# PSU_MAX1831_1V5_ALT.net
KiCad netlist of a schematic drawn in Altium Designer
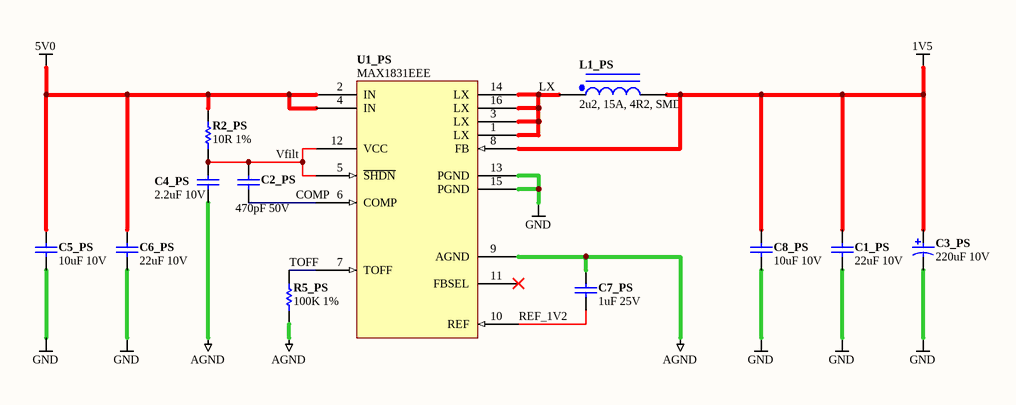
[diagram p0: PSU_MAX1831_1V5_ALT.SchDoc]

(export (version "E")
  (design (tool "Eeschema 10.0.6"))
  (components
    (comp (ref "C1_PS")
      (value "22uF 10V")
      (footprint "CAPC3225-STAR")
      (description "Capacitor, Ceramic, 22uF -20%/+80% 10V 1210 (3225) Y5V")
      (fields (field (name "TOLERANCE") "-20 / +80 %"))
      (libsource (lib "AltiumDesignLibrary") (part "CAP-NP"))
    )
    (comp (ref "C2_PS")
      (value "470pF 50V")
      (footprint "CAPC1005-STAR")
      (description "Capacitor, Ceramic, 470pF 5% 50V 0402 (1005) COG")
      (fields (field (name "TOLERANCE") "5 %"))
      (libsource (lib "AltiumDesignLibrary") (part "CAP-NP"))
    )
    (comp (ref "C3_PS")
      (value "220uF 10V")
      (footprint "CAPC7343-STAR")
      (description "Capacitor, Tantalum, 220uF 10% 10V MCCT-D (7343-31)")
      (fields (field (name "TOLERANCE") "10 %"))
      (libsource (lib "AltiumDesignLibrary") (part "CAP-P"))
    )
    (comp (ref "C4_PS")
      (value "2.2uF 10V")
      (footprint "CAPC1608-STAR")
      (description "Capacitor, Ceramic, 2.2uF 10% 10V 0603 (1608) X5R")
      (fields (field (name "TOLERANCE") "10 %"))
      (libsource (lib "AltiumDesignLibrary") (part "CAP-NP"))
    )
    (comp (ref "C5_PS")
      (value "10uF 10V")
      (footprint "CAPC2012-STAR")
      (description "Capacitor, Ceramic, 10uF 10% 10V 0805 (2012) X5R")
      (fields (field (name "TOLERANCE") "10 %"))
      (libsource (lib "AltiumDesignLibrary") (part "CAP-NP"))
    )
    (comp (ref "C6_PS")
      (value "22uF 10V")
      (footprint "CAPC3225-STAR")
      (description "Capacitor, Ceramic, 22uF -20%/+80% 10V 1210 (3225) Y5V")
      (fields (field (name "TOLERANCE") "-20 / +80 %"))
      (libsource (lib "AltiumDesignLibrary") (part "CAP-NP"))
    )
    (comp (ref "C7_PS")
      (value "1uF 25V")
      (footprint "CAPC3216-STAR")
      (description "Capacitor, Ceramic, 1uF 10% 25V 1206 (3216) X7R")
      (fields (field (name "TOLERANCE") "10 %"))
      (libsource (lib "AltiumDesignLibrary") (part "CAP-NP"))
    )
    (comp (ref "C8_PS")
      (value "10uF 10V")
      (footprint "CAPC2012-STAR")
      (description "Capacitor, Ceramic, 10uF 10% 10V 0805 (2012) X5R")
      (fields (field (name "TOLERANCE") "10 %"))
      (libsource (lib "AltiumDesignLibrary") (part "CAP-NP"))
    )
    (comp (ref "L1_PS")
      (value "2u2, 15A, 4R2, SMD")
      (footprint "IND-EPCOS-SMD-B82559")
      (description "Inductor, 2.2uH, 15A, 4R2, SMD")
      (libsource (lib "AltiumDesignLibrary") (part "IND-IRON-DOT"))
    )
    (comp (ref "R2_PS")
      (value "10R 1%")
      (footprint "RESC1005-STAR")
      (description "Resistor, 10R 1% 0402 (1005)")
      (fields (field (name "TOLERANCE") "1 %"))
      (libsource (lib "AltiumDesignLibrary") (part "RES"))
    )
    (comp (ref "R5_PS")
      (value "100K 1%")
      (footprint "RESC1005-STAR")
      (description "Resistor, 100K 1% 0402 (1005)")
      (fields (field (name "TOLERANCE") "1 %"))
      (libsource (lib "AltiumDesignLibrary") (part "RES"))
    )
    (comp (ref "U1_PS")
      (value "MAX1831EEE")
      (footprint "SOP63P602-16")
      (libsource (lib "AltiumDesignLibrary") (part "MAX1831-ALT"))
    )
  )
  (nets
    (net (code "1") (name "/COMP") (class "Default")
      (node (ref "C2_PS") (pin "2") (pinfunction "2_2") (pintype "passive"))
      (node (ref "U1_PS") (pin "6") (pinfunction "COMP_6") (pintype "input"))
    )
    (net (code "2") (name "/LX") (class "Default")
      (node (ref "L1_PS") (pin "1") (pinfunction "1_1") (pintype "passive"))
      (node (ref "U1_PS") (pin "1") (pinfunction "LX_1") (pintype "power_in"))
      (node (ref "U1_PS") (pin "14") (pinfunction "LX_14") (pintype "power_in"))
      (node (ref "U1_PS") (pin "16") (pinfunction "LX_16") (pintype "power_in"))
      (node (ref "U1_PS") (pin "3") (pinfunction "LX_3") (pintype "power_in"))
    )
    (net (code "3") (name "/REF_1V2") (class "Default")
      (node (ref "C7_PS") (pin "2") (pinfunction "2_2") (pintype "passive"))
      (node (ref "U1_PS") (pin "10") (pinfunction "REF_10") (pintype "input"))
    )
    (net (code "4") (name "/TOFF") (class "Default")
      (node (ref "R5_PS") (pin "1") (pinfunction "1_1") (pintype "passive"))
      (node (ref "U1_PS") (pin "7") (pinfunction "TOFF_7") (pintype "input"))
    )
    (net (code "5") (name "/Vfilt") (class "Default")
      (node (ref "C2_PS") (pin "1") (pinfunction "1_1") (pintype "passive"))
      (node (ref "C4_PS") (pin "1") (pinfunction "1_1") (pintype "passive"))
      (node (ref "R2_PS") (pin "2") (pinfunction "2_2") (pintype "passive"))
      (node (ref "U1_PS") (pin "12") (pinfunction "VCC_12") (pintype "power_in"))
      (node (ref "U1_PS") (pin "5") (pinfunction "~{SHDN}_5") (pintype "input"))
    )
    (net (code "6") (name "1V5") (class "Default")
      (node (ref "C1_PS") (pin "1") (pinfunction "1_1") (pintype "passive"))
      (node (ref "C3_PS") (pin "1") (pinfunction "1_1") (pintype "passive"))
      (node (ref "C8_PS") (pin "1") (pinfunction "1_1") (pintype "passive"))
      (node (ref "L1_PS") (pin "2") (pinfunction "2_2") (pintype "passive"))
      (node (ref "U1_PS") (pin "8") (pinfunction "FB_8") (pintype "input"))
    )
    (net (code "7") (name "5V0") (class "Default")
      (node (ref "C5_PS") (pin "1") (pinfunction "1_1") (pintype "passive"))
      (node (ref "C6_PS") (pin "1") (pinfunction "1_1") (pintype "passive"))
      (node (ref "R2_PS") (pin "1") (pinfunction "1_1") (pintype "passive"))
      (node (ref "U1_PS") (pin "2") (pinfunction "IN_2") (pintype "power_in"))
      (node (ref "U1_PS") (pin "4") (pinfunction "IN_4") (pintype "power_in"))
    )
    (net (code "8") (name "AGND") (class "Default")
      (node (ref "C4_PS") (pin "2") (pinfunction "2_2") (pintype "passive"))
      (node (ref "C7_PS") (pin "1") (pinfunction "1_1") (pintype "passive"))
      (node (ref "R5_PS") (pin "2") (pinfunction "2_2") (pintype "passive"))
      (node (ref "U1_PS") (pin "9") (pinfunction "AGND_9") (pintype "power_in"))
    )
    (net (code "9") (name "GND") (class "Default")
      (node (ref "C1_PS") (pin "2") (pinfunction "2_2") (pintype "passive"))
      (node (ref "C3_PS") (pin "2") (pinfunction "2_2") (pintype "passive"))
      (node (ref "C5_PS") (pin "2") (pinfunction "2_2") (pintype "passive"))
      (node (ref "C6_PS") (pin "2") (pinfunction "2_2") (pintype "passive"))
      (node (ref "C8_PS") (pin "2") (pinfunction "2_2") (pintype "passive"))
      (node (ref "U1_PS") (pin "13") (pinfunction "PGND_13") (pintype "power_in"))
      (node (ref "U1_PS") (pin "15") (pinfunction "PGND_15") (pintype "power_in"))
    )
    (net (code "10") (name "unconnected-(U1_PS-FBSEL-Pad11)") (class "Default")
      (node (ref "U1_PS") (pin "11") (pinfunction "FBSEL_11") (pintype "passive+no_connect"))
    )
  )
)
